# Channel.net
KiCad netlist of a schematic drawn in Altium Designer
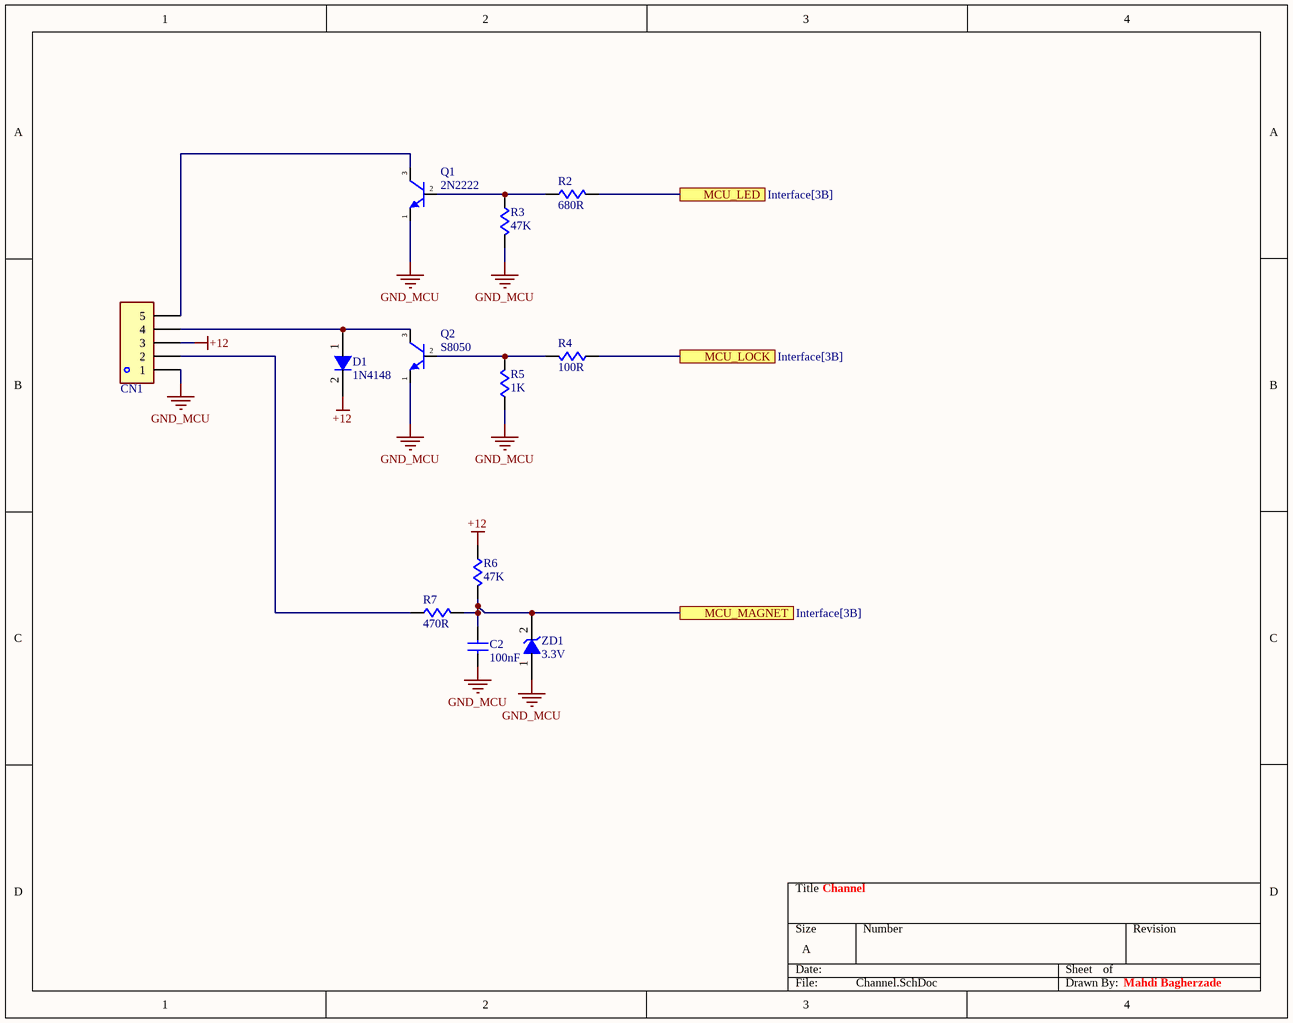
[diagram p0: Channel.SchDoc]

(export (version "E")
  (design (tool "Eeschema 10.0.6"))
  (components
    (comp (ref "C2")
      (value "100nF")
      (footprint "C-0805")
      (description "CAPACITOR")
      (fields
        (field (name "VOLTAGE") "50V")
        (field (name "TOLERANCE") "X7R")
        (field (name "PUBLISHER") "Mahdi Bagherzadeh")
      )
      (libsource (lib "Mahdi-Bagherzadeh") (part "CAP-CER"))
    )
    (comp (ref "CN1")
      (value "Connector XH-Straight-THD-2.54mm")
      (footprint "XH-5")
      (description "CONNECTOR")
      (fields (field (name "PUBLISHER") "Mahdi Bagherzadeh"))
      (libsource (lib "Mahdi-Bagherzadeh") (part "CN-5pin"))
    )
    (comp (ref "D1")
      (value "Diode 1N4148-SMD")
      (footprint "SOD80")
      (description "DIODE")
      (fields (field (name "CODE") "1N4148") (field (name "PUBLISHER") "Mahdi Bagherzadeh"))
      (libsource (lib "Mahdi-Bagherzadeh") (part "DIODE"))
    )
    (comp (ref "Q1")
      (value "2N2222")
      (footprint "SOT23-213")
      (description "TRANSISTOR")
      (fields (field (name "Comment") "TR 2N2222-SMD") (field (name "PUBLISHER") "Mahdi Bagherzadeh"))
      (libsource (lib "Mahdi-Bagherzadeh") (part "2N2222"))
    )
    (comp (ref "Q2")
      (value "S8050")
      (footprint "SOT23-213")
      (description "TRANSISTOR")
      (fields (field (name "Comment") "TR S8050-SMD") (field (name "PUBLISHER") "Mahdi Bagherzadeh"))
      (libsource (lib "Mahdi-Bagherzadeh") (part "S8050"))
    )
    (comp (ref "R2")
      (value "680R")
      (footprint "R-0805")
      (description "RESISTOR")
      (fields
        (field (name "TOLERANCE") "5%")
        (field (name "POWER") "1/8W")
        (field (name "PUBLISHER") "Mahdi Bagherzadeh")
      )
      (libsource (lib "Mahdi-Bagherzadeh") (part "RES"))
    )
    (comp (ref "R3")
      (value "47K")
      (footprint "R-0805")
      (description "RESISTOR")
      (fields
        (field (name "TOLERANCE") "5%")
        (field (name "POWER") "1/8W")
        (field (name "PUBLISHER") "Mahdi Bagherzadeh")
      )
      (libsource (lib "Mahdi-Bagherzadeh") (part "RES"))
    )
    (comp (ref "R4")
      (value "100R")
      (footprint "R-0805")
      (description "RESISTOR")
      (fields
        (field (name "TOLERANCE") "5%")
        (field (name "POWER") "1/8W")
        (field (name "PUBLISHER") "Mahdi Bagherzadeh")
      )
      (libsource (lib "Mahdi-Bagherzadeh") (part "RES"))
    )
    (comp (ref "R5")
      (value "1K")
      (footprint "R-0805")
      (description "RESISTOR")
      (fields
        (field (name "TOLERANCE") "5%")
        (field (name "POWER") "1/8W")
        (field (name "PUBLISHER") "Mahdi Bagherzadeh")
      )
      (libsource (lib "Mahdi-Bagherzadeh") (part "RES"))
    )
    (comp (ref "R6")
      (value "47K")
      (footprint "R-0805")
      (description "RESISTOR")
      (fields
        (field (name "TOLERANCE") "5%")
        (field (name "POWER") "1/8W")
        (field (name "PUBLISHER") "Mahdi Bagherzadeh")
      )
      (libsource (lib "Mahdi-Bagherzadeh") (part "RES"))
    )
    (comp (ref "R7")
      (value "470R")
      (footprint "R-0805")
      (description "RESISTOR")
      (fields
        (field (name "TOLERANCE") "5%")
        (field (name "POWER") "1/8W")
        (field (name "PUBLISHER") "Mahdi Bagherzadeh")
      )
      (libsource (lib "Mahdi-Bagherzadeh") (part "RES"))
    )
    (comp (ref "ZD1")
      (value "Zener -3.3V-SMD")
      (footprint "SOD80")
      (description "DIODE")
      (fields
        (field (name "POWER") "Minimelf")
        (field (name "VOLTAGE") "3.3V")
        (field (name "PUBLISHER") "Mahdi Bagherzadeh")
      )
      (libsource (lib "Mahdi-Bagherzadeh") (part "DIODE-ZENER"))
    )
  )
  (nets
    (net (code "1") (name "+12") (class "Default")
      (node (ref "CN1") (pin "3") (pinfunction "3_3") (pintype "passive"))
      (node (ref "D1") (pin "2") (pinfunction "C_2") (pintype "passive"))
      (node (ref "R6") (pin "1") (pinfunction "1_1") (pintype "passive"))
    )
    (net (code "2") (name "/MCU_LED") (class "Default")
      (node (ref "R2") (pin "2") (pinfunction "2_2") (pintype "passive"))
    )
    (net (code "3") (name "/MCU_LOCK") (class "Default")
      (node (ref "R4") (pin "1") (pinfunction "1_1") (pintype "passive"))
    )
    (net (code "4") (name "/MCU_MAGNET") (class "Default")
      (node (ref "C2") (pin "1") (pinfunction "1_1") (pintype "passive"))
      (node (ref "R6") (pin "2") (pinfunction "2_2") (pintype "passive"))
      (node (ref "R7") (pin "2") (pinfunction "2_2") (pintype "passive"))
      (node (ref "ZD1") (pin "2") (pinfunction "C_2") (pintype "passive"))
    )
    (net (code "5") (name "GND_MCU") (class "Default")
      (node (ref "C2") (pin "2") (pinfunction "2_2") (pintype "passive"))
      (node (ref "CN1") (pin "1") (pinfunction "1_1") (pintype "passive"))
      (node (ref "Q1") (pin "1") (pinfunction "E_1") (pintype "passive"))
      (node (ref "Q2") (pin "1") (pinfunction "E_1") (pintype "passive"))
      (node (ref "R3") (pin "2") (pinfunction "2_2") (pintype "passive"))
      (node (ref "R5") (pin "1") (pinfunction "1_1") (pintype "passive"))
      (node (ref "ZD1") (pin "1") (pinfunction "A_1") (pintype "passive"))
    )
    (net (code "6") (name "Net-(CN1-Pad2)") (class "Default")
      (node (ref "CN1") (pin "2") (pinfunction "2_2") (pintype "passive"))
      (node (ref "R7") (pin "1") (pinfunction "1_1") (pintype "passive"))
    )
    (net (code "7") (name "Net-(D1-A)") (class "Default")
      (node (ref "CN1") (pin "4") (pinfunction "4_4") (pintype "passive"))
      (node (ref "D1") (pin "1") (pinfunction "A_1") (pintype "passive"))
      (node (ref "Q2") (pin "3") (pinfunction "C_3") (pintype "passive"))
    )
    (net (code "8") (name "Net-(Q1-B)") (class "Default")
      (node (ref "Q1") (pin "2") (pinfunction "B_2") (pintype "passive"))
      (node (ref "R2") (pin "1") (pinfunction "1_1") (pintype "passive"))
      (node (ref "R3") (pin "1") (pinfunction "1_1") (pintype "passive"))
    )
    (net (code "9") (name "Net-(Q1-C)") (class "Default")
      (node (ref "CN1") (pin "5") (pinfunction "5_5") (pintype "passive"))
      (node (ref "Q1") (pin "3") (pinfunction "C_3") (pintype "passive"))
    )
    (net (code "10") (name "Net-(Q2-B)") (class "Default")
      (node (ref "Q2") (pin "2") (pinfunction "B_2") (pintype "passive"))
      (node (ref "R4") (pin "2") (pinfunction "2_2") (pintype "passive"))
      (node (ref "R5") (pin "2") (pinfunction "2_2") (pintype "passive"))
    )
  )
)
